# design.net
KiCad netlist of a schematic drawn in EasyEDA Pro
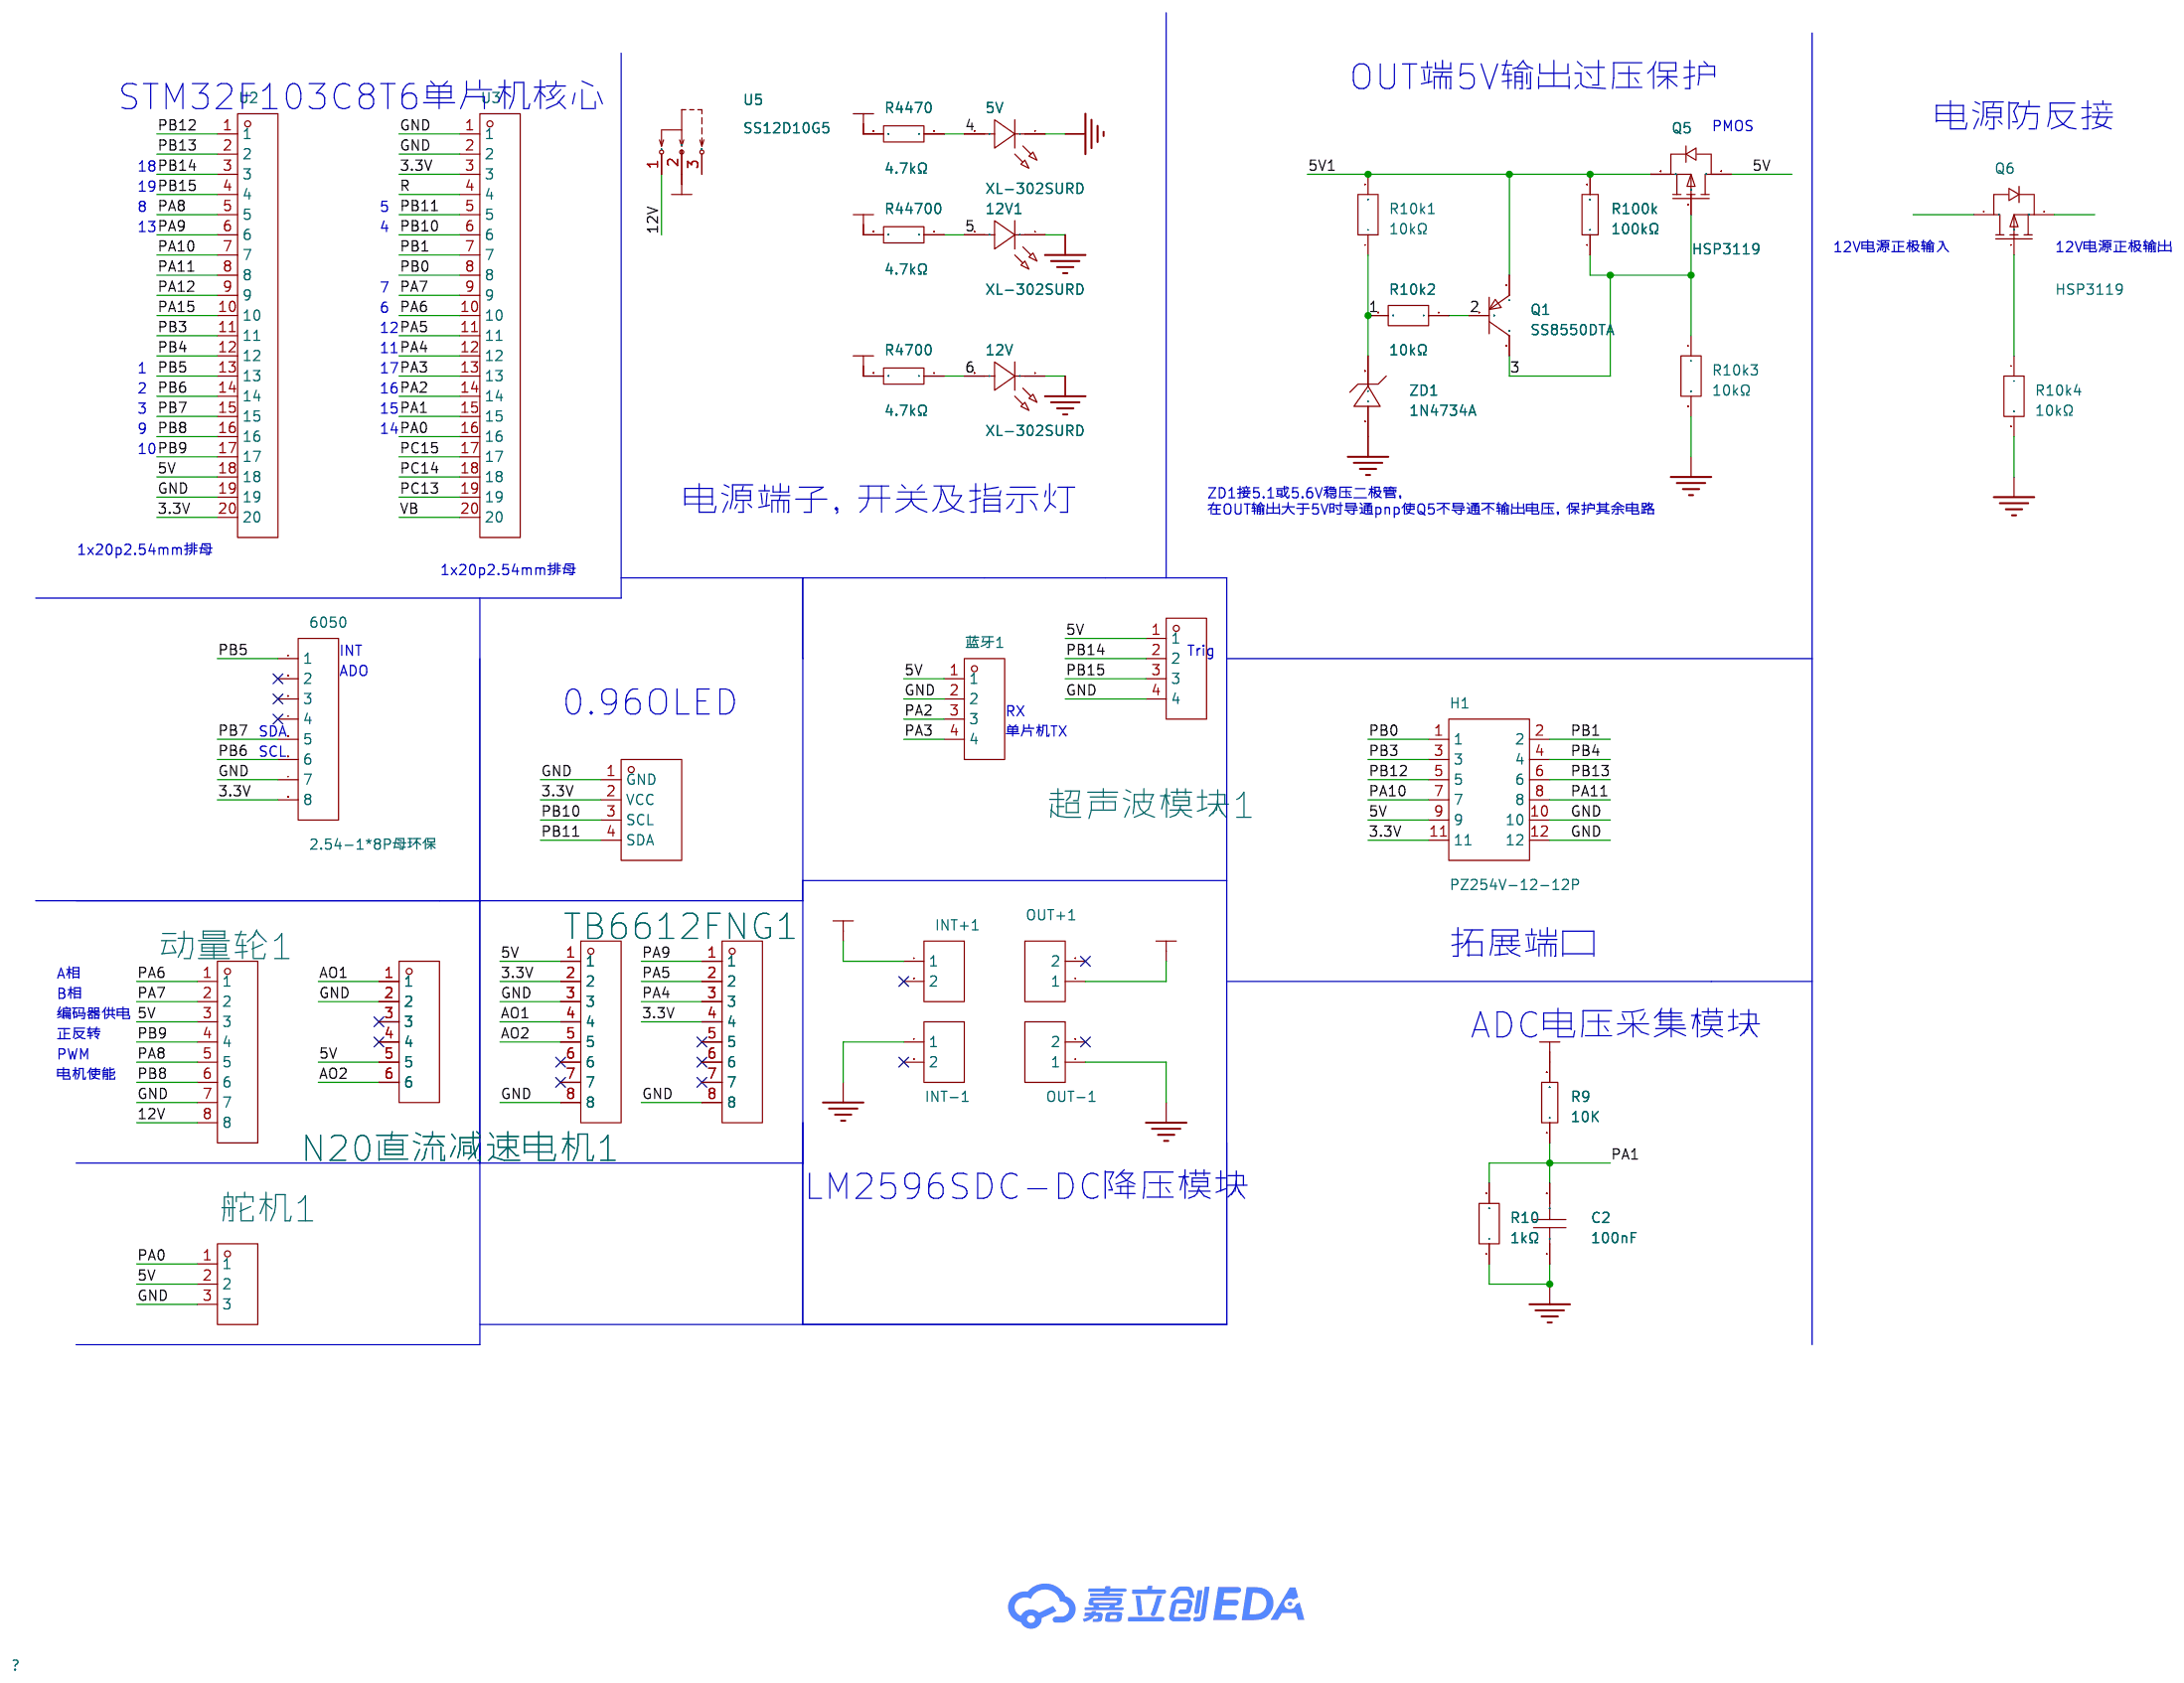
[diagram p0: schematic sheet]

(export (version "E")
  (design (tool "Eeschema 10.0.6"))
  (components
    (comp (ref "5V")
      (value "XL-302SURD")
      (footprint "easyedapro:LED-TH_BD3.8-P2.54-RD")
      (fields (field (name "Manufacturer") "XINGLIGHT(成兴光)"))
      (libsource (lib "easyedapro") (part "XL-302SURD"))
    )
    (comp (ref "12V")
      (value "XL-302SURD")
      (footprint "easyedapro:LED-TH_BD3.8-P2.54-RD")
      (fields (field (name "Manufacturer") "XINGLIGHT(成兴光)"))
      (libsource (lib "easyedapro") (part "XL-302SURD"))
    )
    (comp (ref "12V1")
      (value "XL-302SURD")
      (footprint "easyedapro:LED-TH_BD3.8-P2.54-RD")
      (fields (field (name "Manufacturer") "XINGLIGHT(成兴光)"))
      (libsource (lib "easyedapro") (part "XL-302SURD"))
    )
    (comp (ref "6050")
      (value "2.54-1*8P母环保")
      (footprint "easyedapro:HDR-TH_8P-P2.54-V-F-1")
      (description "插孔结构:1x8P;间距:2.54mm;行距:-;安装类型:直插;排数:单排;总孔位数:8P;塑高:-;触头材质:-;触头镀层:-;")
      (fields (field (name "Manufacturer") "BOOMELE(博穆精密)"))
      (libsource (lib "easyedapro") (part "Header-Female-2.54_1x8"))
    )
    (comp (ref "C2")
      (value "100nF")
      (footprint "easyedapro:C0603")
      (libsource (lib "easyedapro") (part "CapAcitance"))
    )
    (comp (ref "H1")
      (value "PZ254V-12-12P")
      (footprint "easyedapro:HDR-TH_12P-P2.54-V-M-R2-C6-S2.54")
      (fields (field (name "Manufacturer") "XFCN(兴飞)"))
      (libsource (lib "easyedapro") (part "PZ254V-12-12P"))
    )
    (comp (ref "INT+1")
      (value "2.54-1*2P母")
      (footprint "easyedapro:HDR-TH_2P-P2.54-V-F")
      (description "插孔结构:1x2P;间距:2.54mm;行距:-;安装类型:直插;排数:单排;总孔位数:2P;塑高:-;触头材质:-;触头镀层:-;")
      (fields (field (name "Manufacturer") "BOOMELE(博穆精密)"))
      (libsource (lib "easyedapro") (part "Header-Female-2.54_1x2"))
    )
    (comp (ref "INT-1")
      (value "2.54-1*2P母")
      (footprint "easyedapro:HDR-TH_2P-P2.54-V-F")
      (description "插孔结构:1x2P;间距:2.54mm;行距:-;安装类型:直插;排数:单排;总孔位数:2P;塑高:-;触头材质:-;触头镀层:-;")
      (fields (field (name "Manufacturer") "BOOMELE(博穆精密)"))
      (libsource (lib "easyedapro") (part "Header-Female-2.54_1x2"))
    )
    (comp (ref "N20直流减速电机1")
      (value "KH-2PH90-1X6P-L10.5")
      (footprint "easyedapro:HDR-TH_6P-P2.00-H-M-W7.2-N")
      (fields (field (name "Manufacturer") "kinghelm(金航标)"))
      (libsource (lib "easyedapro") (part "KH-2PH90-1X6P-L10.5"))
    )
    (comp (ref "OLED1")
      (value "HS96L03W2C03")
      (footprint "easyedapro:OLED-TH_L27.8-W27.2-P2.54_C9900033791")
      (description "主控芯片:SSD1315;接口类型:I2C;尺寸(inch):0.96;像素分辨率:128x64;")
      (fields (field (name "Manufacturer") "HS(汉昇)"))
      (libsource (lib "easyedapro") (part "HS96L03W2C03"))
    )
    (comp (ref "OUT+1")
      (value "2.54-1*2P母")
      (footprint "easyedapro:HDR-TH_2P-P2.54-V-F")
      (description "插孔结构:1x2P;间距:2.54mm;行距:-;安装类型:直插;排数:单排;总孔位数:2P;塑高:-;触头材质:-;触头镀层:-;")
      (fields (field (name "Manufacturer") "BOOMELE(博穆精密)"))
      (libsource (lib "easyedapro") (part "Header-Female-2.54_1x2"))
    )
    (comp (ref "OUT-1")
      (value "2.54-1*2P母")
      (footprint "easyedapro:HDR-TH_2P-P2.54-V-F")
      (description "插孔结构:1x2P;间距:2.54mm;行距:-;安装类型:直插;排数:单排;总孔位数:2P;塑高:-;触头材质:-;触头镀层:-;")
      (fields (field (name "Manufacturer") "BOOMELE(博穆精密)"))
      (libsource (lib "easyedapro") (part "Header-Female-2.54_1x2"))
    )
    (comp (ref "Q1")
      (value "SS8550DTA")
      (footprint "easyedapro:TO-92-3_L4.8-W3.7-P2.54-L")
      (description "晶体管类型:PNP;集电极电流(Ic):1.5A;集射极击穿电压(Vceo):25V;功率(Pd):2W;直流电流增益(hFE@Ic,Vce):40@800mA,1V;")
      (fields (field (name "Manufacturer") "onsemi(安森美)"))
      (libsource (lib "easyedapro") (part "SS8550DTA"))
    )
    (comp (ref "Q5")
      (value "HSP3119")
      (footprint "easyedapro:TO-220-3_L10.2-W4.5-P2.54-L-1")
      (description "类型:1个P沟道;漏源电压(Vdss):30V;连续漏极电流(Id):150A;导通电阻(RDS(on)):-;耗散功率(Pd):200W;阈值电压(Vgs(th)):2.5V;")
      (fields (field (name "Manufacturer") "HUASHUO(华朔)"))
      (libsource (lib "easyedapro") (part "HSP3119"))
    )
    (comp (ref "Q6")
      (value "HSP3119")
      (footprint "easyedapro:TO-220-3_L10.2-W4.5-P2.54-L-1")
      (description "类型:1个P沟道;漏源电压(Vdss):30V;连续漏极电流(Id):150A;导通电阻(RDS(on)):-;耗散功率(Pd):200W;阈值电压(Vgs(th)):2.5V;")
      (fields (field (name "Manufacturer") "HUASHUO(华朔)"))
      (libsource (lib "easyedapro") (part "HSP3119"))
    )
    (comp (ref "R9") (value "10K") (footprint "easyedapro:R0603") (libsource (lib "easyedapro") (part "电阻")))
    (comp (ref "R10")
      (value "1kΩ")
      (footprint "easyedapro:RES-TH_BD2.3-L6.5-P10.50-D0.5")
      (description "电阻类型:金属膜电阻;阻值:1kΩ;精度:±1%;功率:250mW;温度系数:±200ppm/°C;")
      (fields (field (name "Manufacturer Part") "MF1/4W-1KΩ±1%T52") (field (name "Manufacturer") "华星机电"))
      (libsource (lib "easyedapro") (part "MF1/4W-1KΩ±1%T52"))
    )
    (comp (ref "R10k1")
      (value "10kΩ")
      (footprint "easyedapro:RES-TH_BD2.4-L6.3-P10.30-D0.6")
      (description "电阻类型:金属膜电阻;阻值:10kΩ;精度:±1%;功率:250mW;温度系数:±50ppm/°C;")
      (fields
        (field (name "Manufacturer Part") "RN1/4W10KFT/BA1")
        (field (name "Manufacturer") "Tyohm(幸亚电阻)")
      )
      (libsource (lib "easyedapro") (part "RN 1/4W 10K F T/B A1"))
    )
    (comp (ref "R10k2")
      (value "10kΩ")
      (footprint "easyedapro:RES-TH_BD2.4-L6.3-P10.30-D0.6")
      (description "电阻类型:金属膜电阻;阻值:10kΩ;精度:±1%;功率:250mW;温度系数:±50ppm/°C;")
      (fields
        (field (name "Manufacturer Part") "RN1/4W10KFT/BA1")
        (field (name "Manufacturer") "Tyohm(幸亚电阻)")
      )
      (libsource (lib "easyedapro") (part "RN 1/4W 10K F T/B A1"))
    )
    (comp (ref "R10k3")
      (value "10kΩ")
      (footprint "easyedapro:RES-TH_BD2.4-L6.3-P10.30-D0.6")
      (description "电阻类型:金属膜电阻;阻值:10kΩ;精度:±1%;功率:250mW;温度系数:±50ppm/°C;")
      (fields
        (field (name "Manufacturer Part") "RN1/4W10KFT/BA1")
        (field (name "Manufacturer") "Tyohm(幸亚电阻)")
      )
      (libsource (lib "easyedapro") (part "RN 1/4W 10K F T/B A1"))
    )
    (comp (ref "R10k4")
      (value "10kΩ")
      (footprint "easyedapro:RES-TH_BD2.4-L6.3-P10.30-D0.6")
      (description "电阻类型:金属膜电阻;阻值:10kΩ;精度:±1%;功率:250mW;温度系数:±50ppm/°C;")
      (fields
        (field (name "Manufacturer Part") "RN1/4W10KFT/BA1")
        (field (name "Manufacturer") "Tyohm(幸亚电阻)")
      )
      (libsource (lib "easyedapro") (part "RN 1/4W 10K F T/B A1"))
    )
    (comp (ref "R100k")
      (value "100kΩ")
      (footprint "easyedapro:RES-TH_BD2.7-L6.2-P10.20-D0.4")
      (description "电阻类型:金属膜电阻;阻值:100kΩ;精度:±1%;功率:250mW;温度系数:±350ppm/°C;")
      (fields (field (name "Manufacturer Part") "MF1/4W-100K±1%-OT26") (field (name "Manufacturer") "VO(翔胜)"))
      (libsource (lib "easyedapro") (part "MF1/4W-100K±1%-OT26"))
    )
    (comp (ref "R4470")
      (value "4.7kΩ")
      (footprint "easyedapro:R0402")
      (description "电阻类型:厚膜电阻;阻值:4.7kΩ;精度:±1%;功率:62.5mW;最大工作电压:50V;温度系数:±100ppm/°C;")
      (fields
        (field (name "Manufacturer Part") "0402WGF4701TCE")
        (field (name "Manufacturer") "UNI-ROYAL(厚声)")
      )
      (libsource (lib "easyedapro") (part "0402WGF4701TCE"))
    )
    (comp (ref "R4700")
      (value "4.7kΩ")
      (footprint "easyedapro:R0402")
      (description "电阻类型:厚膜电阻;阻值:4.7kΩ;精度:±1%;功率:62.5mW;最大工作电压:50V;温度系数:±100ppm/°C;")
      (fields
        (field (name "Manufacturer Part") "0402WGF4701TCE")
        (field (name "Manufacturer") "UNI-ROYAL(厚声)")
      )
      (libsource (lib "easyedapro") (part "0402WGF4701TCE"))
    )
    (comp (ref "R44700")
      (value "4.7kΩ")
      (footprint "easyedapro:R0402")
      (description "电阻类型:厚膜电阻;阻值:4.7kΩ;精度:±1%;功率:62.5mW;最大工作电压:50V;温度系数:±100ppm/°C;")
      (fields
        (field (name "Manufacturer Part") "0402WGF4701TCE")
        (field (name "Manufacturer") "UNI-ROYAL(厚声)")
      )
      (libsource (lib "easyedapro") (part "0402WGF4701TCE"))
    )
    (comp (ref "TB1")
      (value "2.54-1*8P/30mm(3+24+3)")
      (footprint "easyedapro:HDR-TH_8P-P2.54-V-M-4")
      (libsource (lib "easyedapro") (part "2.54-1*8P/30MM(3+24+3)"))
    )
    (comp (ref "TB6612FNG1")
      (value "2.54-1*8P/30mm(3+24+3)")
      (footprint "easyedapro:HDR-TH_8P-P2.54-V-M-4")
      (libsource (lib "easyedapro") (part "2.54-1*8P/30MM(3+24+3)"))
    )
    (comp (ref "U2")
      (value "KH-2FH-1X20P-H4.3")
      (footprint "easyedapro:HDR-TH_20P-P2.00-V-F-A")
      (fields (field (name "Manufacturer") "kinghelm(金航标)"))
      (libsource (lib "easyedapro") (part "KH-2FH-1X20P-H4.3"))
    )
    (comp (ref "U3")
      (value "KH-2FH-1X20P-H4.3")
      (footprint "easyedapro:HDR-TH_20P-P2.00-V-F-A")
      (fields (field (name "Manufacturer") "kinghelm(金航标)"))
      (libsource (lib "easyedapro") (part "KH-2FH-1X20P-H4.3"))
    )
    (comp (ref "U5")
      (value "SS12D10G5")
      (footprint "easyedapro:SW-TH_SHOU-HAN_SS12D10G4")
      (description "电路结构:单刀双掷;安装方式:直插;额定电流(DC):2A;额定电压(DC):125V;机械寿命:3千次;")
      (fields (field (name "Manufacturer") "SHOU HAN(首韩)"))
      (libsource (lib "easyedapro") (part "SS12D10G5"))
    )
    (comp (ref "ZD1")
      (value "1N4734A")
      (footprint "easyedapro:DO-41_BD2.8-L4.2-P8.00-D0.7-FD")
      (description "二极管配置:独立式;稳压值(标称值):5.6V;耗散功率(Pd):-;")
      (fields (field (name "Manufacturer") "ST(先科)"))
      (libsource (lib "easyedapro") (part "1N4734A_C41430"))
    )
    (comp (ref "动量轮1")
      (value "2.54-1*8P/30mm(3+24+3)")
      (footprint "easyedapro:HDR-TH_8P-P2.54-V-M-4")
      (libsource (lib "easyedapro") (part "2.54-1*8P/30MM(3+24+3)"))
    )
    (comp (ref "舵机1")
      (value "PM254V-11-03-H85")
      (footprint "easyedapro:HDR-TH_3P-P2.54-V-F")
      (description "插孔结构:1x3P;间距:2.54mm;行距:-;安装类型:直插;排数:单排;总孔位数:3P;塑高:-;触头材质:黄铜;触头镀层:-;")
      (fields (field (name "Manufacturer") "XFCN(兴飞)"))
      (libsource (lib "easyedapro") (part "PM254V-11-03-H85"))
    )
    (comp (ref "蓝牙1")
      (value "2.54-1*4P母")
      (fields (field (name "Manufacturer") "BOOMELE(博穆精密)"))
      (libsource (lib "easyedapro") (part "2.54-1*4P母"))
    )
    (comp (ref "超声波模块1")
      (value "KH-2.54FH-1X4P-H8.5")
      (fields (field (name "Manufacturer") "kinghelm(金航标)"))
      (libsource (lib "easyedapro") (part "KH-2.54FH-1X4P-H8.5"))
    )
  )
  (nets
    (net (code "1") (name "/1") (class "Default")
      (node (ref "R10k1") (pin "1") (pinfunction "1_1") (pintype "unspecified"))
      (node (ref "R10k2") (pin "2") (pinfunction "2_2") (pintype "unspecified"))
      (node (ref "ZD1") (pin "2") (pinfunction "K_2") (pintype "unspecified"))
    )
    (net (code "2") (name "/2") (class "Default")
      (node (ref "Q1") (pin "2") (pinfunction "B_2") (pintype "unspecified"))
      (node (ref "R10k2") (pin "1") (pinfunction "1_1") (pintype "unspecified"))
    )
    (net (code "3") (name "/3") (class "Default")
      (node (ref "Q1") (pin "3") (pinfunction "C_3") (pintype "unspecified"))
      (node (ref "Q5") (pin "1") (pinfunction "G_1") (pintype "unspecified"))
      (node (ref "R100k") (pin "1") (pinfunction "1_1") (pintype "unspecified"))
      (node (ref "R10k3") (pin "1") (pinfunction "1_1") (pintype "unspecified"))
    )
    (net (code "4") (name "/3.3V") (class "Default")
      (node (ref "6050") (pin "8") (pinfunction "8_8") (pintype "input"))
      (node (ref "H1") (pin "11") (pinfunction "11_11") (pintype "unspecified"))
      (node (ref "OLED1") (pin "2") (pinfunction "VCC_2") (pintype "unspecified"))
      (node (ref "TB1") (pin "4") (pinfunction "4_4") (pintype "unspecified"))
      (node (ref "TB6612FNG1") (pin "2") (pinfunction "2_2") (pintype "unspecified"))
      (node (ref "U2") (pin "20") (pinfunction "20_20") (pintype "unspecified"))
      (node (ref "U3") (pin "3") (pinfunction "3_3") (pintype "unspecified"))
    )
    (net (code "5") (name "/4") (class "Default")
      (node (ref "5V") (pin "2") (pinfunction "A_2") (pintype "unspecified"))
      (node (ref "R4470") (pin "1") (pinfunction "1_1") (pintype "input"))
    )
    (net (code "6") (name "/5") (class "Default")
      (node (ref "12V1") (pin "2") (pinfunction "A_2") (pintype "unspecified"))
      (node (ref "R44700") (pin "1") (pinfunction "1_1") (pintype "input"))
    )
    (net (code "7") (name "/6") (class "Default")
      (node (ref "12V") (pin "2") (pinfunction "A_2") (pintype "unspecified"))
      (node (ref "R4700") (pin "1") (pinfunction "1_1") (pintype "input"))
    )
    (net (code "8") (name "/AO1") (class "Default")
      (node (ref "N20直流减速电机1") (pin "1") (pinfunction "1_1") (pintype "unspecified"))
      (node (ref "TB6612FNG1") (pin "4") (pinfunction "4_4") (pintype "unspecified"))
    )
    (net (code "9") (name "/AO2") (class "Default")
      (node (ref "N20直流减速电机1") (pin "6") (pinfunction "6_6") (pintype "unspecified"))
      (node (ref "TB6612FNG1") (pin "5") (pinfunction "5_5") (pintype "unspecified"))
    )
    (net (code "10") (name "/PA0") (class "Default")
      (node (ref "U3") (pin "16") (pinfunction "16_16") (pintype "unspecified"))
      (node (ref "舵机1") (pin "1") (pinfunction "1_1") (pintype "unspecified"))
    )
    (net (code "11") (name "/PA1") (class "Default")
      (node (ref "C2") (pin "2") (pinfunction "2_2") (pintype "input"))
      (node (ref "R10") (pin "2") (pinfunction "2_2") (pintype "unspecified"))
      (node (ref "R9") (pin "1") (pinfunction "1_1") (pintype "input"))
      (node (ref "U3") (pin "15") (pinfunction "15_15") (pintype "unspecified"))
    )
    (net (code "12") (name "/PA2") (class "Default")
      (node (ref "U3") (pin "14") (pinfunction "14_14") (pintype "unspecified"))
      (node (ref "蓝牙1") (pin "3") (pinfunction "3_3") (pintype "unspecified"))
    )
    (net (code "13") (name "/PA3") (class "Default")
      (node (ref "U3") (pin "13") (pinfunction "13_13") (pintype "unspecified"))
      (node (ref "蓝牙1") (pin "4") (pinfunction "4_4") (pintype "unspecified"))
    )
    (net (code "14") (name "/PA4") (class "Default")
      (node (ref "TB1") (pin "3") (pinfunction "3_3") (pintype "unspecified"))
      (node (ref "U3") (pin "12") (pinfunction "12_12") (pintype "unspecified"))
    )
    (net (code "15") (name "/PA5") (class "Default")
      (node (ref "TB1") (pin "2") (pinfunction "2_2") (pintype "unspecified"))
      (node (ref "U3") (pin "11") (pinfunction "11_11") (pintype "unspecified"))
    )
    (net (code "16") (name "/PA6") (class "Default")
      (node (ref "U3") (pin "10") (pinfunction "10_10") (pintype "unspecified"))
      (node (ref "动量轮1") (pin "1") (pinfunction "1_1") (pintype "unspecified"))
    )
    (net (code "17") (name "/PA7") (class "Default")
      (node (ref "U3") (pin "9") (pinfunction "9_9") (pintype "unspecified"))
      (node (ref "动量轮1") (pin "2") (pinfunction "2_2") (pintype "unspecified"))
    )
    (net (code "18") (name "/PA8") (class "Default")
      (node (ref "U2") (pin "5") (pinfunction "5_5") (pintype "unspecified"))
      (node (ref "动量轮1") (pin "5") (pinfunction "5_5") (pintype "unspecified"))
    )
    (net (code "19") (name "/PA9") (class "Default")
      (node (ref "TB1") (pin "1") (pinfunction "1_1") (pintype "unspecified"))
      (node (ref "U2") (pin "6") (pinfunction "6_6") (pintype "unspecified"))
    )
    (net (code "20") (name "/PA10") (class "Default")
      (node (ref "H1") (pin "7") (pinfunction "7_7") (pintype "unspecified"))
      (node (ref "U2") (pin "7") (pinfunction "7_7") (pintype "unspecified"))
    )
    (net (code "21") (name "/PA11") (class "Default")
      (node (ref "H1") (pin "8") (pinfunction "8_8") (pintype "unspecified"))
      (node (ref "U2") (pin "8") (pinfunction "8_8") (pintype "unspecified"))
    )
    (net (code "22") (name "/PA12") (class "Default")
      (node (ref "U2") (pin "9") (pinfunction "9_9") (pintype "unspecified"))
    )
    (net (code "23") (name "/PA15") (class "Default")
      (node (ref "U2") (pin "10") (pinfunction "10_10") (pintype "unspecified"))
    )
    (net (code "24") (name "/PB0") (class "Default")
      (node (ref "H1") (pin "1") (pinfunction "1_1") (pintype "unspecified"))
      (node (ref "U3") (pin "8") (pinfunction "8_8") (pintype "unspecified"))
    )
    (net (code "25") (name "/PB1") (class "Default")
      (node (ref "H1") (pin "2") (pinfunction "2_2") (pintype "unspecified"))
      (node (ref "U3") (pin "7") (pinfunction "7_7") (pintype "unspecified"))
    )
    (net (code "26") (name "/PB3") (class "Default")
      (node (ref "H1") (pin "3") (pinfunction "3_3") (pintype "unspecified"))
      (node (ref "U2") (pin "11") (pinfunction "11_11") (pintype "unspecified"))
    )
    (net (code "27") (name "/PB4") (class "Default")
      (node (ref "H1") (pin "4") (pinfunction "4_4") (pintype "unspecified"))
      (node (ref "U2") (pin "12") (pinfunction "12_12") (pintype "unspecified"))
    )
    (net (code "28") (name "/PB5") (class "Default")
      (node (ref "6050") (pin "1") (pinfunction "1_1") (pintype "input"))
      (node (ref "U2") (pin "13") (pinfunction "13_13") (pintype "unspecified"))
    )
    (net (code "29") (name "/PB6") (class "Default")
      (node (ref "6050") (pin "6") (pinfunction "6_6") (pintype "input"))
      (node (ref "U2") (pin "14") (pinfunction "14_14") (pintype "unspecified"))
    )
    (net (code "30") (name "/PB7") (class "Default")
      (node (ref "6050") (pin "5") (pinfunction "5_5") (pintype "input"))
      (node (ref "U2") (pin "15") (pinfunction "15_15") (pintype "unspecified"))
    )
    (net (code "31") (name "/PB8") (class "Default")
      (node (ref "U2") (pin "16") (pinfunction "16_16") (pintype "unspecified"))
      (node (ref "动量轮1") (pin "6") (pinfunction "6_6") (pintype "unspecified"))
    )
    (net (code "32") (name "/PB9") (class "Default")
      (node (ref "U2") (pin "17") (pinfunction "17_17") (pintype "unspecified"))
      (node (ref "动量轮1") (pin "4") (pinfunction "4_4") (pintype "unspecified"))
    )
    (net (code "33") (name "/PB10") (class "Default")
      (node (ref "OLED1") (pin "3") (pinfunction "SCL_3") (pintype "unspecified"))
      (node (ref "U3") (pin "6") (pinfunction "6_6") (pintype "unspecified"))
    )
    (net (code "34") (name "/PB11") (class "Default")
      (node (ref "OLED1") (pin "4") (pinfunction "SDA_4") (pintype "unspecified"))
      (node (ref "U3") (pin "5") (pinfunction "5_5") (pintype "unspecified"))
    )
    (net (code "35") (name "/PB12") (class "Default")
      (node (ref "H1") (pin "5") (pinfunction "5_5") (pintype "unspecified"))
      (node (ref "U2") (pin "1") (pinfunction "1_1") (pintype "unspecified"))
    )
    (net (code "36") (name "/PB13") (class "Default")
      (node (ref "H1") (pin "6") (pinfunction "6_6") (pintype "unspecified"))
      (node (ref "U2") (pin "2") (pinfunction "2_2") (pintype "unspecified"))
    )
    (net (code "37") (name "/PB14") (class "Default")
      (node (ref "U2") (pin "3") (pinfunction "3_3") (pintype "unspecified"))
      (node (ref "超声波模块1") (pin "2") (pinfunction "2_2") (pintype "unspecified"))
    )
    (net (code "38") (name "/PB15") (class "Default")
      (node (ref "U2") (pin "4") (pinfunction "4_4") (pintype "unspecified"))
      (node (ref "超声波模块1") (pin "3") (pinfunction "3_3") (pintype "unspecified"))
    )
    (net (code "39") (name "/PC13") (class "Default")
      (node (ref "U3") (pin "19") (pinfunction "19_19") (pintype "unspecified"))
    )
    (net (code "40") (name "/PC14") (class "Default")
      (node (ref "U3") (pin "18") (pinfunction "18_18") (pintype "unspecified"))
    )
    (net (code "41") (name "/PC15") (class "Default")
      (node (ref "U3") (pin "17") (pinfunction "17_17") (pintype "unspecified"))
    )
    (net (code "42") (name "/R") (class "Default")
      (node (ref "U3") (pin "4") (pinfunction "4_4") (pintype "unspecified"))
    )
    (net (code "43") (name "/VB") (class "Default")
      (node (ref "U3") (pin "20") (pinfunction "20_20") (pintype "unspecified"))
    )
    (net (code "44") (name "5V") (class "Default")
      (node (ref "H1") (pin "9") (pinfunction "9_9") (pintype "unspecified"))
      (node (ref "N20直流减速电机1") (pin "5") (pinfunction "5_5") (pintype "unspecified"))
      (node (ref "Q5") (pin "2") (pinfunction "D_2") (pintype "unspecified"))
      (node (ref "R4470") (pin "2") (pinfunction "2_2") (pintype "input"))
      (node (ref "TB6612FNG1") (pin "1") (pinfunction "1_1") (pintype "unspecified"))
      (node (ref "U2") (pin "18") (pinfunction "18_18") (pintype "unspecified"))
      (node (ref "动量轮1") (pin "3") (pinfunction "3_3") (pintype "unspecified"))
      (node (ref "舵机1") (pin "2") (pinfunction "2_2") (pintype "unspecified"))
      (node (ref "蓝牙1") (pin "1") (pinfunction "1_1") (pintype "unspecified"))
      (node (ref "超声波模块1") (pin "1") (pinfunction "1_1") (pintype "unspecified"))
    )
    (net (code "45") (name "5V1") (class "Default")
      (node (ref "OUT+1") (pin "1") (pinfunction "1_1") (pintype "input"))
      (node (ref "Q1") (pin "1") (pinfunction "E_1") (pintype "unspecified"))
      (node (ref "Q5") (pin "3") (pinfunction "S_3") (pintype "unspecified"))
      (node (ref "R100k") (pin "2") (pinfunction "2_2") (pintype "unspecified"))
      (node (ref "R10k1") (pin "2") (pinfunction "2_2") (pintype "unspecified"))
    )
    (net (code "46") (name "12V") (class "Default")
      (node (ref "INT+1") (pin "1") (pinfunction "1_1") (pintype "input"))
      (node (ref "R4700") (pin "2") (pinfunction "2_2") (pintype "input"))
      (node (ref "R9") (pin "2") (pinfunction "2_2") (pintype "input"))
      (node (ref "U5") (pin "1") (pinfunction "1_1") (pintype "unspecified"))
      (node (ref "动量轮1") (pin "8") (pinfunction "8_8") (pintype "unspecified"))
    )
    (net (code "47") (name "12V1") (class "Default")
      (node (ref "R44700") (pin "2") (pinfunction "2_2") (pintype "input"))
      (node (ref "U5") (pin "2") (pinfunction "2_2") (pintype "unspecified"))
    )
    (net (code "48") (name "GND") (class "Default")
      (node (ref "12V") (pin "1") (pinfunction "K_1") (pintype "unspecified"))
      (node (ref "12V1") (pin "1") (pinfunction "K_1") (pintype "unspecified"))
      (node (ref "5V") (pin "1") (pinfunction "K_1") (pintype "unspecified"))
      (node (ref "6050") (pin "7") (pinfunction "7_7") (pintype "input"))
      (node (ref "C2") (pin "1") (pinfunction "1_1") (pintype "input"))
      (node (ref "H1") (pin "10") (pinfunction "10_10") (pintype "unspecified"))
      (node (ref "H1") (pin "12") (pinfunction "12_12") (pintype "unspecified"))
      (node (ref "INT-1") (pin "1") (pinfunction "1_1") (pintype "input"))
      (node (ref "N20直流减速电机1") (pin "2") (pinfunction "2_2") (pintype "unspecified"))
      (node (ref "OLED1") (pin "1") (pinfunction "GND_1") (pintype "unspecified"))
      (node (ref "OUT-1") (pin "1") (pinfunction "1_1") (pintype "input"))
      (node (ref "R10") (pin "1") (pinfunction "1_1") (pintype "unspecified"))
      (node (ref "R10k3") (pin "2") (pinfunction "2_2") (pintype "unspecified"))
      (node (ref "R10k4") (pin "2") (pinfunction "2_2") (pintype "unspecified"))
      (node (ref "TB1") (pin "8") (pinfunction "8_8") (pintype "unspecified"))
      (node (ref "TB6612FNG1") (pin "3") (pinfunction "3_3") (pintype "unspecified"))
      (node (ref "TB6612FNG1") (pin "8") (pinfunction "8_8") (pintype "unspecified"))
      (node (ref "U2") (pin "19") (pinfunction "19_19") (pintype "unspecified"))
      (node (ref "U3") (pin "1") (pinfunction "1_1") (pintype "unspecified"))
      (node (ref "U3") (pin "2") (pinfunction "2_2") (pintype "unspecified"))
      (node (ref "ZD1") (pin "1") (pinfunction "A_1") (pintype "unspecified"))
      (node (ref "动量轮1") (pin "7") (pinfunction "7_7") (pintype "unspecified"))
      (node (ref "舵机1") (pin "3") (pinfunction "3_3") (pintype "unspecified"))
      (node (ref "蓝牙1") (pin "2") (pinfunction "2_2") (pintype "unspecified"))
      (node (ref "超声波模块1") (pin "4") (pinfunction "4_4") (pintype "unspecified"))
    )
    (net (code "49") (name "Net-(Q6-G)") (class "Default")
      (node (ref "Q6") (pin "1") (pinfunction "G_1") (pintype "unspecified"))
      (node (ref "R10k4") (pin "1") (pinfunction "1_1") (pintype "unspecified"))
    )
    (net (code "50") (name "unconnected-(6050-Pad2)") (class "Default")
      (node (ref "6050") (pin "2") (pinfunction "2_2") (pintype "input+no_connect"))
    )
    (net (code "51") (name "unconnected-(6050-Pad3)") (class "Default")
      (node (ref "6050") (pin "3") (pinfunction "3_3") (pintype "input+no_connect"))
    )
    (net (code "52") (name "unconnected-(6050-Pad4)") (class "Default")
      (node (ref "6050") (pin "4") (pinfunction "4_4") (pintype "input+no_connect"))
    )
    (net (code "53") (name "unconnected-(INT+1-Pad2)") (class "Default")
      (node (ref "INT+1") (pin "2") (pinfunction "2_2") (pintype "input+no_connect"))
    )
    (net (code "54") (name "unconnected-(INT-1-Pad2)") (class "Default")
      (node (ref "INT-1") (pin "2") (pinfunction "2_2") (pintype "input+no_connect"))
    )
    (net (code "55") (name "unconnected-(N20直流减速电机1-Pad3)") (class "Default")
      (node (ref "N20直流减速电机1") (pin "3") (pinfunction "3_3") (pintype "unspecified+no_connect"))
    )
    (net (code "56") (name "unconnected-(N20直流减速电机1-Pad4)") (class "Default")
      (node (ref "N20直流减速电机1") (pin "4") (pinfunction "4_4") (pintype "unspecified+no_connect"))
    )
    (net (code "57") (name "unconnected-(OUT+1-Pad2)") (class "Default")
      (node (ref "OUT+1") (pin "2") (pinfunction "2_2") (pintype "input+no_connect"))
    )
    (net (code "58") (name "unconnected-(OUT-1-Pad2)") (class "Default")
      (node (ref "OUT-1") (pin "2") (pinfunction "2_2") (pintype "input+no_connect"))
    )
    (net (code "59") (name "unconnected-(Q6-D-Pad2)") (class "Default")
      (node (ref "Q6") (pin "2") (pinfunction "D_2") (pintype "unspecified"))
    )
    (net (code "60") (name "unconnected-(Q6-S-Pad3)") (class "Default")
      (node (ref "Q6") (pin "3") (pinfunction "S_3") (pintype "unspecified"))
    )
    (net (code "61") (name "unconnected-(TB1-Pad5)") (class "Default")
      (node (ref "TB1") (pin "5") (pinfunction "5_5") (pintype "unspecified+no_connect"))
    )
    (net (code "62") (name "unconnected-(TB1-Pad6)") (class "Default")
      (node (ref "TB1") (pin "6") (pinfunction "6_6") (pintype "unspecified+no_connect"))
    )
    (net (code "63") (name "unconnected-(TB1-Pad7)") (class "Default")
      (node (ref "TB1") (pin "7") (pinfunction "7_7") (pintype "unspecified+no_connect"))
    )
    (net (code "64") (name "unconnected-(TB6612FNG1-Pad6)") (class "Default")
      (node (ref "TB6612FNG1") (pin "6") (pinfunction "6_6") (pintype "unspecified+no_connect"))
    )
    (net (code "65") (name "unconnected-(TB6612FNG1-Pad7)") (class "Default")
      (node (ref "TB6612FNG1") (pin "7") (pinfunction "7_7") (pintype "unspecified+no_connect"))
    )
    (net (code "66") (name "unconnected-(U5-Pad3)") (class "Default")
      (node (ref "U5") (pin "3") (pinfunction "3_3") (pintype "unspecified"))
    )
  )
)
